# uc.net
KiCad netlist of a schematic drawn in Altium Designer
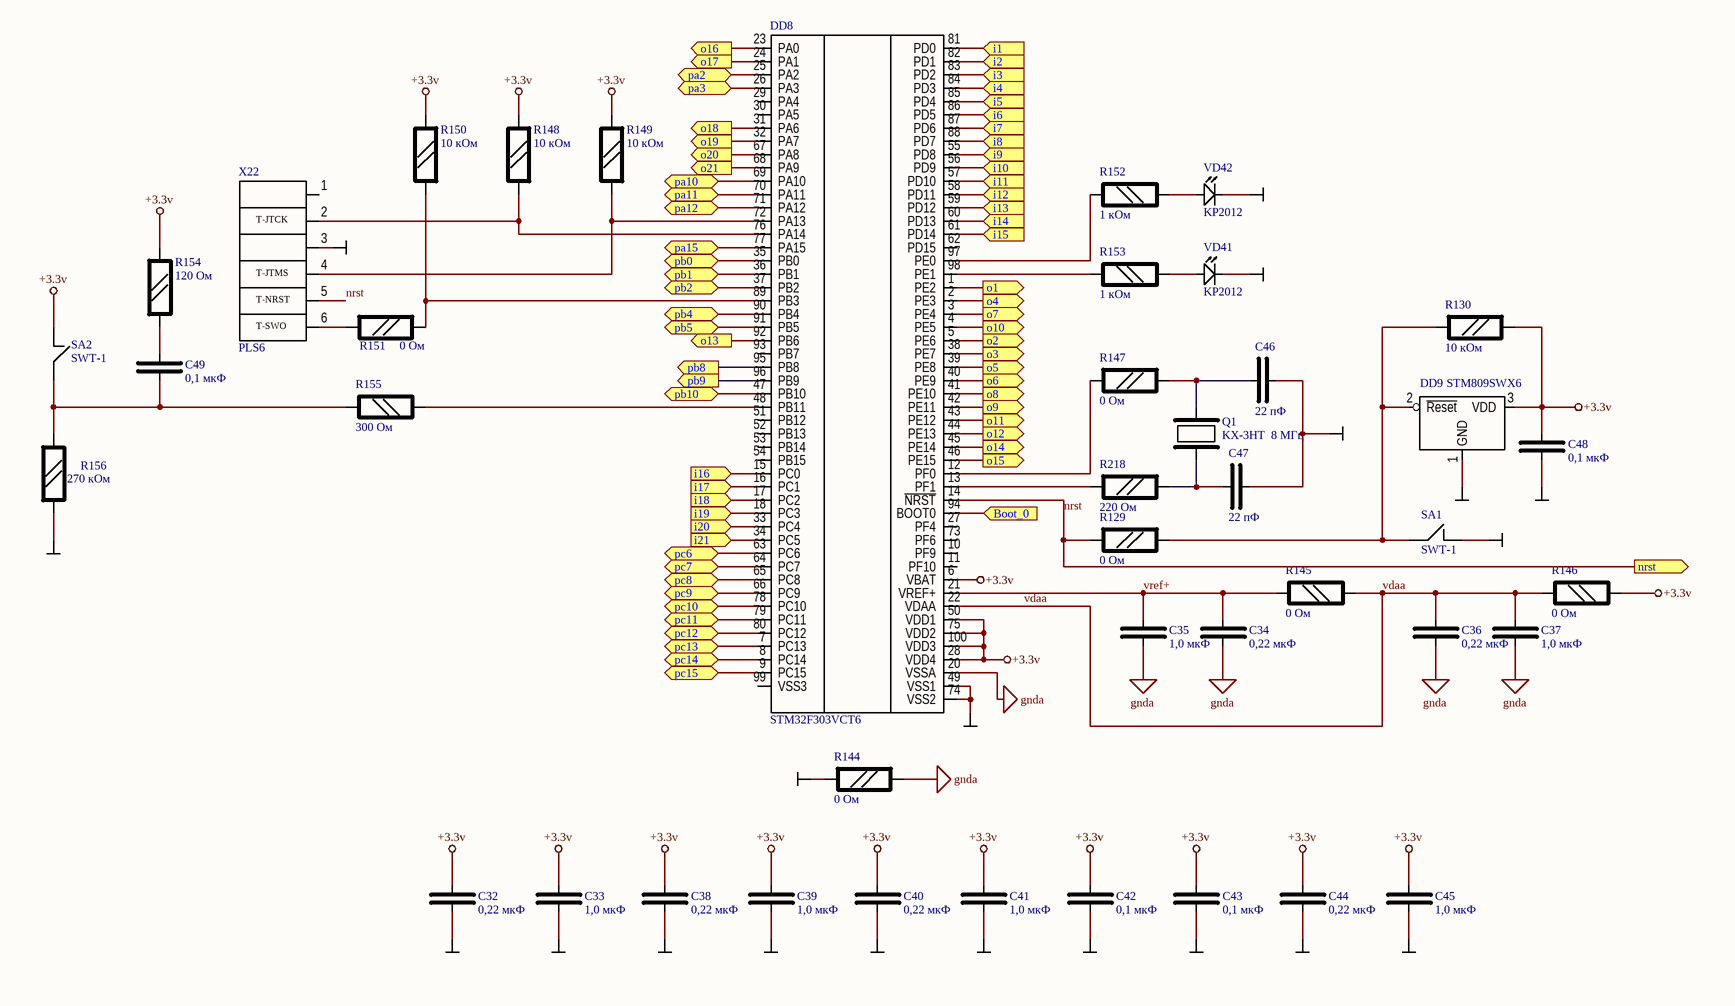
[diagram p0: uc.SchDoc]

(export (version "E")
  (design (tool "Eeschema 10.0.6"))
  (components
    (comp (ref "C32")
      (value "0,22 мкФ")
      (footprint "SMD0805CAP")
      (description "Чип конденсатор 0805")
      (fields (field (name "VOLTAGE") "50V"))
      (libsource (lib "SL02_22F") (part "C0805"))
    )
    (comp (ref "C33")
      (value "1,0 мкФ")
      (footprint "SMD0805CAP")
      (description "Чип конденсатор 0805")
      (fields (field (name "VOLTAGE") "50V"))
      (libsource (lib "SL02_22F") (part "C0805"))
    )
    (comp (ref "C34")
      (value "0,22 мкФ")
      (footprint "SMD0805CAP")
      (description "Чип конденсатор 0805")
      (fields (field (name "VOLTAGE") "50V"))
      (libsource (lib "SL02_22F") (part "C0805"))
    )
    (comp (ref "C35")
      (value "1,0 мкФ")
      (footprint "SMD0805CAP")
      (description "Чип конденсатор 0805")
      (fields (field (name "VOLTAGE") "50V"))
      (libsource (lib "SL02_22F") (part "C0805"))
    )
    (comp (ref "C36")
      (value "0,22 мкФ")
      (footprint "SMD0805CAP")
      (description "Чип конденсатор 0805")
      (fields (field (name "VOLTAGE") "50V"))
      (libsource (lib "SL02_22F") (part "C0805"))
    )
    (comp (ref "C37")
      (value "1,0 мкФ")
      (footprint "SMD0805CAP")
      (description "Чип конденсатор 0805")
      (fields (field (name "VOLTAGE") "50V"))
      (libsource (lib "SL02_22F") (part "C0805"))
    )
    (comp (ref "C38")
      (value "0,22 мкФ")
      (footprint "SMD0805CAP")
      (description "Чип конденсатор 0805")
      (fields (field (name "VOLTAGE") "50V"))
      (libsource (lib "SL02_22F") (part "C0805"))
    )
    (comp (ref "C39")
      (value "1,0 мкФ")
      (footprint "SMD0805CAP")
      (description "Чип конденсатор 0805")
      (fields (field (name "VOLTAGE") "50V"))
      (libsource (lib "SL02_22F") (part "C0805"))
    )
    (comp (ref "C40")
      (value "0,22 мкФ")
      (footprint "SMD0805CAP")
      (description "Чип конденсатор 0805")
      (fields (field (name "VOLTAGE") "50V"))
      (libsource (lib "SL02_22F") (part "C0805"))
    )
    (comp (ref "C41")
      (value "1,0 мкФ")
      (footprint "SMD0805CAP")
      (description "Чип конденсатор 0805")
      (fields (field (name "VOLTAGE") "50V"))
      (libsource (lib "SL02_22F") (part "C0805"))
    )
    (comp (ref "C42")
      (value "0,1 мкФ")
      (footprint "SMD0805CAP")
      (description "Чип конденсатор 0805")
      (fields (field (name "VOLTAGE") "50V"))
      (libsource (lib "SL02_22F") (part "C0805"))
    )
    (comp (ref "C43")
      (value "0,1 мкФ")
      (footprint "SMD0805CAP")
      (description "Чип конденсатор 0805")
      (fields (field (name "VOLTAGE") "50V"))
      (libsource (lib "SL02_22F") (part "C0805"))
    )
    (comp (ref "C44")
      (value "0,22 мкФ")
      (footprint "SMD0805CAP")
      (description "Чип конденсатор 0805")
      (fields (field (name "VOLTAGE") "50V"))
      (libsource (lib "SL02_22F") (part "C0805"))
    )
    (comp (ref "C45")
      (value "1,0 мкФ")
      (footprint "SMD0805CAP")
      (description "Чип конденсатор 0805")
      (fields (field (name "VOLTAGE") "50V"))
      (libsource (lib "SL02_22F") (part "C0805"))
    )
    (comp (ref "C46")
      (value "22 пФ")
      (footprint "SMD0805CAP")
      (description "Чип конденсатор 0805")
      (fields (field (name "VOLTAGE") "50V"))
      (libsource (lib "SL02_22F") (part "C0805"))
    )
    (comp (ref "C47")
      (value "22 пФ")
      (footprint "SMD0805CAP")
      (description "Чип конденсатор 0805")
      (fields (field (name "VOLTAGE") "50V"))
      (libsource (lib "SL02_22F") (part "C0805"))
    )
    (comp (ref "C48")
      (value "0,1 мкФ")
      (footprint "SMD0805CAP")
      (description "Чип конденсатор 0805")
      (fields (field (name "VOLTAGE") "50V"))
      (libsource (lib "SL02_22F") (part "C0805"))
    )
    (comp (ref "C49")
      (value "0,1 мкФ")
      (footprint "SMD0805CAP")
      (description "Чип конденсатор 0805")
      (fields (field (name "VOLTAGE") "50V"))
      (libsource (lib "SL02_22F") (part "C0805"))
    )
    (comp (ref "DD8")
      (value "STM32F303VCT6")
      (footprint "LQFP100")
      (description "ARM Cortex3")
      (libsource (lib "SL02_22F") (part "STM32F303VCT6"))
    )
    (comp (ref "DD9")
      (value "STM809SWX6")
      (footprint "SOT-23")
      (description "Reset генератор")
      (fields (field (name "VOLTAGE") "3V3"))
      (libsource (lib "L02_22F") (part "STM809SWX6"))
    )
    (comp (ref "Q1")
      (value "KX-3HT  8 МГц")
      (footprint "HC49_S")
      (description "Резонатор кварцевый")
      (libsource (lib "SL02_22F") (part "KX-3HT"))
    )
    (comp (ref "R129")
      (value "0 Ом")
      (footprint "SMD0805RES")
      (description "Чип резистор 0805")
      (fields (field (name "TOLERANCE") "5%"))
      (libsource (lib "SL02_22F") (part "R0805"))
    )
    (comp (ref "R130")
      (value "10 кОм")
      (footprint "SMD0805RES")
      (description "Чип резистор 0805")
      (fields (field (name "TOLERANCE") "5%"))
      (libsource (lib "SL02_22F") (part "R0805"))
    )
    (comp (ref "R144")
      (value "0 Ом")
      (footprint "SMD0805RES")
      (description "Чип резистор 0805")
      (fields (field (name "TOLERANCE") "5%"))
      (libsource (lib "SL02_22F") (part "R0805"))
    )
    (comp (ref "R145")
      (value "0 Ом")
      (footprint "SMD0805RES")
      (description "Чип резистор 0805")
      (fields (field (name "TOLERANCE") "5%"))
      (libsource (lib "SL02_22F") (part "R0805"))
    )
    (comp (ref "R146")
      (value "0 Ом")
      (footprint "SMD0805RES")
      (description "Чип резистор 0805")
      (fields (field (name "TOLERANCE") "5%"))
      (libsource (lib "SL02_22F") (part "R0805"))
    )
    (comp (ref "R147")
      (value "0 Ом")
      (footprint "SMD0805RES")
      (description "Чип резистор 0805")
      (fields (field (name "TOLERANCE") "5%"))
      (libsource (lib "SL02_22F") (part "R0805"))
    )
    (comp (ref "R148")
      (value "10 кОм")
      (footprint "SMD0805RES")
      (description "Чип резистор 0805")
      (fields (field (name "TOLERANCE") "1%"))
      (libsource (lib "SL02_22F") (part "R0805"))
    )
    (comp (ref "R149")
      (value "10 кОм")
      (footprint "SMD0805RES")
      (description "Чип резистор 0805")
      (fields (field (name "TOLERANCE") "1%"))
      (libsource (lib "SL02_22F") (part "R0805"))
    )
    (comp (ref "R150")
      (value "10 кОм")
      (footprint "SMD0805RES")
      (description "Чип резистор 0805")
      (fields (field (name "TOLERANCE") "1%"))
      (libsource (lib "SL02_22F") (part "R0805"))
    )
    (comp (ref "R151")
      (value "0 Ом")
      (footprint "SMD0805RES")
      (description "Чип резистор 0805")
      (fields (field (name "TOLERANCE") "5%"))
      (libsource (lib "SL02_22F") (part "R0805"))
    )
    (comp (ref "R152")
      (value "1 кОм")
      (footprint "SMD0805RES")
      (description "Чип резистор 0805")
      (fields (field (name "TOLERANCE") "5%"))
      (libsource (lib "SL02_22F") (part "R0805"))
    )
    (comp (ref "R153")
      (value "1 кОм")
      (footprint "SMD0805RES")
      (description "Чип резистор 0805")
      (fields (field (name "TOLERANCE") "5%"))
      (libsource (lib "SL02_22F") (part "R0805"))
    )
    (comp (ref "R154")
      (value "120 Ом")
      (footprint "SMD0805RES")
      (description "Чип резистор 0805")
      (fields (field (name "TOLERANCE") "5%"))
      (libsource (lib "SL02_22F") (part "R0805"))
    )
    (comp (ref "R155")
      (value "300 Ом")
      (footprint "SMD0805RES")
      (description "Чип резистор 0805")
      (fields (field (name "TOLERANCE") "5%"))
      (libsource (lib "SL02_22F") (part "R0805"))
    )
    (comp (ref "R156")
      (value "270 кОм")
      (footprint "SMD0805RES")
      (description "Чип резистор 0805")
      (fields (field (name "TOLERANCE") "5%"))
      (libsource (lib "SL02_22F") (part "R0805"))
    )
    (comp (ref "R218")
      (value "220 Ом")
      (footprint "SMD0805RES")
      (description "Чип резистор 0805")
      (fields (field (name "TOLERANCE") "5%"))
      (libsource (lib "SL02_22F") (part "R0805"))
    )
    (comp (ref "SA1")
      (value "SWT-1")
      (footprint "SWT-1")
      (description "Кнопка тактовая")
      (fields (field (name "VOLTAGE") "12"))
      (libsource (lib "L02_22F") (part "SWT1"))
    )
    (comp (ref "SA2")
      (value "SWT-1")
      (footprint "SWT-1")
      (description "Кнопка тактовая")
      (fields (field (name "VOLTAGE") "12"))
      (libsource (lib "L02_22F") (part "SWT1"))
    )
    (comp (ref "VD41")
      (value "KP2012")
      (footprint "SMD0805DIO_C")
      (description "Чип светодиод 0805")
      (libsource (lib "L02_22F") (part "KP2012_C"))
    )
    (comp (ref "VD42")
      (value "KP2012")
      (footprint "SMD0805DIO_C")
      (description "Чип светодиод 0805")
      (libsource (lib "L02_22F") (part "KP2012_C"))
    )
    (comp (ref "X22")
      (value "PLS6")
      (footprint "PLS6")
      (description "Вилка  PLS 6x2.54")
      (libsource (lib "L02_22F") (part "PLS6"))
    )
  )
  (nets
    (net (code "1") (name "+3.3v") (class "Default")
      (node (ref "C32") (pin "1") (pinfunction "1_1") (pintype "passive"))
      (node (ref "C33") (pin "1") (pinfunction "1_1") (pintype "passive"))
      (node (ref "C38") (pin "1") (pinfunction "1_1") (pintype "passive"))
      (node (ref "C39") (pin "1") (pinfunction "1_1") (pintype "passive"))
      (node (ref "C40") (pin "1") (pinfunction "1_1") (pintype "passive"))
      (node (ref "C41") (pin "1") (pinfunction "1_1") (pintype "passive"))
      (node (ref "C42") (pin "1") (pinfunction "1_1") (pintype "passive"))
      (node (ref "C43") (pin "1") (pinfunction "1_1") (pintype "passive"))
      (node (ref "C44") (pin "1") (pinfunction "1_1") (pintype "passive"))
      (node (ref "C45") (pin "1") (pinfunction "1_1") (pintype "passive"))
      (node (ref "C48") (pin "1") (pinfunction "1_1") (pintype "passive"))
      (node (ref "DD8") (pin "100") (pinfunction "VDD3_100") (pintype "passive"))
      (node (ref "DD8") (pin "28") (pinfunction "VDD4_28") (pintype "passive"))
      (node (ref "DD8") (pin "50") (pinfunction "VDD1_50") (pintype "passive"))
      (node (ref "DD8") (pin "6") (pinfunction "VBAT_6") (pintype "passive"))
      (node (ref "DD8") (pin "75") (pinfunction "VDD2_75") (pintype "passive"))
      (node (ref "DD9") (pin "3") (pinfunction "VDD_3") (pintype "power_in"))
      (node (ref "R130") (pin "2") (pinfunction "2_2") (pintype "passive"))
      (node (ref "R146") (pin "1") (pinfunction "1_1") (pintype "passive"))
      (node (ref "R148") (pin "2") (pinfunction "2_2") (pintype "passive"))
      (node (ref "R149") (pin "2") (pinfunction "2_2") (pintype "passive"))
      (node (ref "R150") (pin "2") (pinfunction "2_2") (pintype "passive"))
      (node (ref "R154") (pin "1") (pinfunction "1_1") (pintype "passive"))
      (node (ref "SA2") (pin "2") (pinfunction "2_2") (pintype "passive"))
    )
    (net (code "2") (name "/i1") (class "Default")
      (node (ref "DD8") (pin "81") (pinfunction "PD0_81") (pintype "passive"))
    )
    (net (code "3") (name "/i2") (class "Default")
      (node (ref "DD8") (pin "82") (pinfunction "PD1_82") (pintype "passive"))
    )
    (net (code "4") (name "/i3") (class "Default")
      (node (ref "DD8") (pin "83") (pinfunction "PD2_83") (pintype "passive"))
    )
    (net (code "5") (name "/i4") (class "Default")
      (node (ref "DD8") (pin "84") (pinfunction "PD3_84") (pintype "passive"))
    )
    (net (code "6") (name "/i5") (class "Default")
      (node (ref "DD8") (pin "85") (pinfunction "PD4_85") (pintype "passive"))
    )
    (net (code "7") (name "/i6") (class "Default")
      (node (ref "DD8") (pin "86") (pinfunction "PD5_86") (pintype "passive"))
    )
    (net (code "8") (name "/i7") (class "Default")
      (node (ref "DD8") (pin "87") (pinfunction "PD6_87") (pintype "passive"))
    )
    (net (code "9") (name "/i8") (class "Default")
      (node (ref "DD8") (pin "88") (pinfunction "PD7_88") (pintype "passive"))
    )
    (net (code "10") (name "/i9") (class "Default")
      (node (ref "DD8") (pin "55") (pinfunction "PD8_55") (pintype "passive"))
    )
    (net (code "11") (name "/i10") (class "Default")
      (node (ref "DD8") (pin "56") (pinfunction "PD9_56") (pintype "passive"))
    )
    (net (code "12") (name "/i11") (class "Default")
      (node (ref "DD8") (pin "57") (pinfunction "PD10_57") (pintype "passive"))
    )
    (net (code "13") (name "/i12") (class "Default")
      (node (ref "DD8") (pin "58") (pinfunction "PD11_58") (pintype "passive"))
    )
    (net (code "14") (name "/i13") (class "Default")
      (node (ref "DD8") (pin "59") (pinfunction "PD12_59") (pintype "passive"))
    )
    (net (code "15") (name "/i14") (class "Default")
      (node (ref "DD8") (pin "60") (pinfunction "PD13_60") (pintype "passive"))
    )
    (net (code "16") (name "/i15") (class "Default")
      (node (ref "DD8") (pin "61") (pinfunction "PD14_61") (pintype "passive"))
    )
    (net (code "17") (name "/i16") (class "Default")
      (node (ref "DD8") (pin "15") (pinfunction "PC0_15") (pintype "passive"))
    )
    (net (code "18") (name "/i17") (class "Default")
      (node (ref "DD8") (pin "16") (pinfunction "PC1_16") (pintype "passive"))
    )
    (net (code "19") (name "/i18") (class "Default")
      (node (ref "DD8") (pin "17") (pinfunction "PC2_17") (pintype "passive"))
    )
    (net (code "20") (name "/i19") (class "Default")
      (node (ref "DD8") (pin "18") (pinfunction "PC3_18") (pintype "passive"))
    )
    (net (code "21") (name "/i20") (class "Default")
      (node (ref "DD8") (pin "33") (pinfunction "PC4_33") (pintype "passive"))
    )
    (net (code "22") (name "/i21") (class "Default")
      (node (ref "DD8") (pin "34") (pinfunction "PC5_34") (pintype "passive"))
    )
    (net (code "23") (name "/nrst") (class "Default")
      (node (ref "DD8") (pin "14") (pinfunction "NRST_14") (pintype "passive"))
      (node (ref "R129") (pin "1") (pinfunction "1_1") (pintype "passive"))
      (node (ref "X22") (pin "5") (pinfunction "5_5") (pintype "passive"))
    )
    (net (code "24") (name "/o1") (class "Default")
      (node (ref "DD8") (pin "1") (pinfunction "PE2_1") (pintype "passive"))
    )
    (net (code "25") (name "/o2") (class "Default")
      (node (ref "DD8") (pin "5") (pinfunction "PE6_5") (pintype "passive"))
    )
    (net (code "26") (name "/o3") (class "Default")
      (node (ref "DD8") (pin "38") (pinfunction "PE7_38") (pintype "passive"))
    )
    (net (code "27") (name "/o4") (class "Default")
      (node (ref "DD8") (pin "2") (pinfunction "PE3_2") (pintype "passive"))
    )
    (net (code "28") (name "/o5") (class "Default")
      (node (ref "DD8") (pin "39") (pinfunction "PE8_39") (pintype "passive"))
    )
    (net (code "29") (name "/o6") (class "Default")
      (node (ref "DD8") (pin "40") (pinfunction "PE9_40") (pintype "passive"))
    )
    (net (code "30") (name "/o7") (class "Default")
      (node (ref "DD8") (pin "3") (pinfunction "PE4_3") (pintype "passive"))
    )
    (net (code "31") (name "/o8") (class "Default")
      (node (ref "DD8") (pin "41") (pinfunction "PE10_41") (pintype "passive"))
    )
    (net (code "32") (name "/o9") (class "Default")
      (node (ref "DD8") (pin "42") (pinfunction "PE11_42") (pintype "passive"))
    )
    (net (code "33") (name "/o10") (class "Default")
      (node (ref "DD8") (pin "4") (pinfunction "PE5_4") (pintype "passive"))
    )
    (net (code "34") (name "/o11") (class "Default")
      (node (ref "DD8") (pin "43") (pinfunction "PE12_43") (pintype "passive"))
    )
    (net (code "35") (name "/o12") (class "Default")
      (node (ref "DD8") (pin "44") (pinfunction "PE13_44") (pintype "passive"))
    )
    (net (code "36") (name "/o13") (class "Default")
      (node (ref "DD8") (pin "92") (pinfunction "PB6_92") (pintype "passive"))
    )
    (net (code "37") (name "/o14") (class "Default")
      (node (ref "DD8") (pin "45") (pinfunction "PE14_45") (pintype "passive"))
    )
    (net (code "38") (name "/o15") (class "Default")
      (node (ref "DD8") (pin "46") (pinfunction "PE15_46") (pintype "passive"))
    )
    (net (code "39") (name "/o16") (class "Default")
      (node (ref "DD8") (pin "23") (pinfunction "PA0_23") (pintype "passive"))
    )
    (net (code "40") (name "/o17") (class "Default")
      (node (ref "DD8") (pin "24") (pinfunction "PA1_24") (pintype "passive"))
    )
    (net (code "41") (name "/o18") (class "Default")
      (node (ref "DD8") (pin "31") (pinfunction "PA6_31") (pintype "passive"))
    )
    (net (code "42") (name "/o19") (class "Default")
      (node (ref "DD8") (pin "32") (pinfunction "PA7_32") (pintype "passive"))
    )
    (net (code "43") (name "/o20") (class "Default")
      (node (ref "DD8") (pin "67") (pinfunction "PA8_67") (pintype "passive"))
    )
    (net (code "44") (name "/o21") (class "Default")
      (node (ref "DD8") (pin "68") (pinfunction "PA9_68") (pintype "passive"))
    )
    (net (code "45") (name "/pa2") (class "Default")
      (node (ref "DD8") (pin "25") (pinfunction "PA2_25") (pintype "passive"))
    )
    (net (code "46") (name "/pa3") (class "Default")
      (node (ref "DD8") (pin "26") (pinfunction "PA3_26") (pintype "passive"))
    )
    (net (code "47") (name "/pa10") (class "Default")
      (node (ref "DD8") (pin "69") (pinfunction "PA10_69") (pintype "passive"))
    )
    (net (code "48") (name "/pa11") (class "Default")
      (node (ref "DD8") (pin "70") (pinfunction "PA11_70") (pintype "passive"))
    )
    (net (code "49") (name "/pa12") (class "Default")
      (node (ref "DD8") (pin "71") (pinfunction "PA12_71") (pintype "passive"))
    )
    (net (code "50") (name "/pa15") (class "Default")
      (node (ref "DD8") (pin "77") (pinfunction "PA15_77") (pintype "passive"))
    )
    (net (code "51") (name "/pb0") (class "Default")
      (node (ref "DD8") (pin "35") (pinfunction "PB0_35") (pintype "passive"))
    )
    (net (code "52") (name "/pb1") (class "Default")
      (node (ref "DD8") (pin "36") (pinfunction "PB1_36") (pintype "passive"))
    )
    (net (code "53") (name "/pb2") (class "Default")
      (node (ref "DD8") (pin "37") (pinfunction "PB2_37") (pintype "passive"))
    )
    (net (code "54") (name "/pb4") (class "Default")
      (node (ref "DD8") (pin "90") (pinfunction "PB4_90") (pintype "passive"))
    )
    (net (code "55") (name "/pb5") (class "Default")
      (node (ref "DD8") (pin "91") (pinfunction "PB5_91") (pintype "passive"))
    )
    (net (code "56") (name "/pb8") (class "Default")
      (node (ref "DD8") (pin "95") (pinfunction "PB8_95") (pintype "passive"))
    )
    (net (code "57") (name "/pb9") (class "Default")
      (node (ref "DD8") (pin "96") (pinfunction "PB9_96") (pintype "passive"))
    )
    (net (code "58") (name "/pb10") (class "Default")
      (node (ref "DD8") (pin "47") (pinfunction "PB10_47") (pintype "passive"))
    )
    (net (code "59") (name "/pс6") (class "Default")
      (node (ref "DD8") (pin "63") (pinfunction "PC6_63") (pintype "passive"))
    )
    (net (code "60") (name "/pс7") (class "Default")
      (node (ref "DD8") (pin "64") (pinfunction "PC7_64") (pintype "passive"))
    )
    (net (code "61") (name "/pс8") (class "Default")
      (node (ref "DD8") (pin "65") (pinfunction "PC8_65") (pintype "passive"))
    )
    (net (code "62") (name "/pс9") (class "Default")
      (node (ref "DD8") (pin "66") (pinfunction "PC9_66") (pintype "passive"))
    )
    (net (code "63") (name "/pс10") (class "Default")
      (node (ref "DD8") (pin "78") (pinfunction "PC10_78") (pintype "passive"))
    )
    (net (code "64") (name "/pс11") (class "Default")
      (node (ref "DD8") (pin "79") (pinfunction "PC11_79") (pintype "passive"))
    )
    (net (code "65") (name "/pс12") (class "Default")
      (node (ref "DD8") (pin "80") (pinfunction "PC12_80") (pintype "passive"))
    )
    (net (code "66") (name "/pс13") (class "Default")
      (node (ref "DD8") (pin "7") (pinfunction "PC13_7") (pintype "passive"))
    )
    (net (code "67") (name "/pс14") (class "Default")
      (node (ref "DD8") (pin "8") (pinfunction "PC14_8") (pintype "passive"))
    )
    (net (code "68") (name "/pс15") (class "Default")
      (node (ref "DD8") (pin "9") (pinfunction "PC15_9") (pintype "passive"))
    )
    (net (code "69") (name "/vdaa") (class "Default")
      (node (ref "C36") (pin "1") (pinfunction "1_1") (pintype "passive"))
      (node (ref "C37") (pin "1") (pinfunction "1_1") (pintype "passive"))
      (node (ref "DD8") (pin "22") (pinfunction "VDAA_22") (pintype "passive"))
      (node (ref "R145") (pin "1") (pinfunction "1_1") (pintype "passive"))
      (node (ref "R146") (pin "2") (pinfunction "2_2") (pintype "passive"))
    )
    (net (code "70") (name "/vref+") (class "Default")
      (node (ref "C34") (pin "1") (pinfunction "1_1") (pintype "passive"))
      (node (ref "C35") (pin "1") (pinfunction "1_1") (pintype "passive"))
      (node (ref "DD8") (pin "21") (pinfunction "VREF+_21") (pintype "passive"))
      (node (ref "R145") (pin "2") (pinfunction "2_2") (pintype "passive"))
    )
    (net (code "71") (name "/Вооt_0") (class "Default")
      (node (ref "DD8") (pin "94") (pinfunction "BOOT0_94") (pintype "passive"))
    )
    (net (code "72") (name "GND") (class "Default")
      (node (ref "C32") (pin "2") (pinfunction "2_2") (pintype "passive"))
      (node (ref "C33") (pin "2") (pinfunction "2_2") (pintype "passive"))
      (node (ref "C38") (pin "2") (pinfunction "2_2") (pintype "passive"))
      (node (ref "C39") (pin "2") (pinfunction "2_2") (pintype "passive"))
      (node (ref "C40") (pin "2") (pinfunction "2_2") (pintype "passive"))
      (node (ref "C41") (pin "2") (pinfunction "2_2") (pintype "passive"))
      (node (ref "C42") (pin "2") (pinfunction "2_2") (pintype "passive"))
      (node (ref "C43") (pin "2") (pinfunction "2_2") (pintype "passive"))
      (node (ref "C44") (pin "2") (pinfunction "2_2") (pintype "passive"))
      (node (ref "C45") (pin "2") (pinfunction "2_2") (pintype "passive"))
      (node (ref "C46") (pin "2") (pinfunction "2_2") (pintype "passive"))
      (node (ref "C47") (pin "2") (pinfunction "2_2") (pintype "passive"))
      (node (ref "C48") (pin "2") (pinfunction "2_2") (pintype "passive"))
      (node (ref "DD8") (pin "49") (pinfunction "VSS1_49") (pintype "passive"))
      (node (ref "DD8") (pin "74") (pinfunction "VSS2_74") (pintype "passive"))
      (node (ref "DD9") (pin "1") (pinfunction "GND_1") (pintype "power_in"))
      (node (ref "R144") (pin "1") (pinfunction "1_1") (pintype "passive"))
      (node (ref "R156") (pin "2") (pinfunction "2_2") (pintype "passive"))
      (node (ref "SA1") (pin "2") (pinfunction "2_2") (pintype "passive"))
      (node (ref "VD41") (pin "1") (pinfunction "Cathode_1") (pintype "passive"))
      (node (ref "VD42") (pin "1") (pinfunction "Cathode_1") (pintype "passive"))
      (node (ref "X22") (pin "3") (pinfunction "3_3") (pintype "passive"))
    )
    (net (code "73") (name "Net-(C46-Pad1)") (class "Default")
      (node (ref "C46") (pin "1") (pinfunction "1_1") (pintype "passive"))
      (node (ref "Q1") (pin "1") (pinfunction "1_1") (pintype "passive"))
      (node (ref "R147") (pin "2") (pinfunction "2_2") (pintype "passive"))
    )
    (net (code "74") (name "Net-(C47-Pad1)") (class "Default")
      (node (ref "C47") (pin "1") (pinfunction "1_1") (pintype "passive"))
      (node (ref "Q1") (pin "2") (pinfunction "2_2") (pintype "passive"))
      (node (ref "R218") (pin "2") (pinfunction "2_2") (pintype "passive"))
    )
    (net (code "75") (name "Net-(C49-Pad1)") (class "Default")
      (node (ref "C49") (pin "1") (pinfunction "1_1") (pintype "passive"))
      (node (ref "R154") (pin "2") (pinfunction "2_2") (pintype "passive"))
    )
    (net (code "76") (name "Net-(C49-Pad2)") (class "Default")
      (node (ref "C49") (pin "2") (pinfunction "2_2") (pintype "passive"))
      (node (ref "R155") (pin "2") (pinfunction "2_2") (pintype "passive"))
      (node (ref "R156") (pin "1") (pinfunction "1_1") (pintype "passive"))
      (node (ref "SA2") (pin "1") (pinfunction "1_1") (pintype "passive"))
    )
    (net (code "77") (name "Net-(DD8-PA13)") (class "Default")
      (node (ref "DD8") (pin "72") (pinfunction "PA13_72") (pintype "passive"))
      (node (ref "R149") (pin "1") (pinfunction "1_1") (pintype "passive"))
      (node (ref "X22") (pin "4") (pinfunction "4_4") (pintype "passive"))
    )
    (net (code "78") (name "Net-(DD8-PA14)") (class "Default")
      (node (ref "DD8") (pin "76") (pinfunction "PA14_76") (pintype "passive"))
      (node (ref "R148") (pin "1") (pinfunction "1_1") (pintype "passive"))
      (node (ref "X22") (pin "2") (pinfunction "2_2") (pintype "passive"))
    )
    (net (code "79") (name "Net-(DD8-PB3)") (class "Default")
      (node (ref "DD8") (pin "89") (pinfunction "PB3_89") (pintype "passive"))
      (node (ref "R150") (pin "1") (pinfunction "1_1") (pintype "passive"))
      (node (ref "R151") (pin "2") (pinfunction "2_2") (pintype "passive"))
    )
    (net (code "80") (name "Net-(DD8-PB11)") (class "Default")
      (node (ref "DD8") (pin "48") (pinfunction "PB11_48") (pintype "passive"))
      (node (ref "R155") (pin "1") (pinfunction "1_1") (pintype "passive"))
    )
    (net (code "81") (name "Net-(DD8-PE0)") (class "Default")
      (node (ref "DD8") (pin "97") (pinfunction "PE0_97") (pintype "passive"))
      (node (ref "R152") (pin "1") (pinfunction "1_1") (pintype "passive"))
    )
    (net (code "82") (name "Net-(DD8-PE1)") (class "Default")
      (node (ref "DD8") (pin "98") (pinfunction "PE1_98") (pintype "passive"))
      (node (ref "R153") (pin "1") (pinfunction "1_1") (pintype "passive"))
    )
    (net (code "83") (name "Net-(DD8-PF0)") (class "Default")
      (node (ref "DD8") (pin "12") (pinfunction "PF0_12") (pintype "passive"))
      (node (ref "R147") (pin "1") (pinfunction "1_1") (pintype "passive"))
    )
    (net (code "84") (name "Net-(DD8-PF1)") (class "Default")
      (node (ref "DD8") (pin "13") (pinfunction "PF1_13") (pintype "passive"))
      (node (ref "R218") (pin "1") (pinfunction "1_1") (pintype "passive"))
    )
    (net (code "85") (name "Net-(DD9-Reset)") (class "Default")
      (node (ref "DD9") (pin "2") (pinfunction "Reset_2") (pintype "output"))
      (node (ref "R129") (pin "2") (pinfunction "2_2") (pintype "passive"))
      (node (ref "R130") (pin "1") (pinfunction "1_1") (pintype "passive"))
      (node (ref "SA1") (pin "1") (pinfunction "1_1") (pintype "passive"))
    )
    (net (code "86") (name "Net-(R151-Pad1)") (class "Default")
      (node (ref "R151") (pin "1") (pinfunction "1_1") (pintype "passive"))
      (node (ref "X22") (pin "6") (pinfunction "6_6") (pintype "passive"))
    )
    (net (code "87") (name "Net-(VD41-Anode)") (class "Default")
      (node (ref "R153") (pin "2") (pinfunction "2_2") (pintype "passive"))
      (node (ref "VD41") (pin "2") (pinfunction "Anode_2") (pintype "passive"))
    )
    (net (code "88") (name "Net-(VD42-Anode)") (class "Default")
      (node (ref "R152") (pin "2") (pinfunction "2_2") (pintype "passive"))
      (node (ref "VD42") (pin "2") (pinfunction "Anode_2") (pintype "passive"))
    )
    (net (code "89") (name "gnda") (class "Default")
      (node (ref "C34") (pin "2") (pinfunction "2_2") (pintype "passive"))
      (node (ref "C35") (pin "2") (pinfunction "2_2") (pintype "passive"))
      (node (ref "C36") (pin "2") (pinfunction "2_2") (pintype "passive"))
      (node (ref "C37") (pin "2") (pinfunction "2_2") (pintype "passive"))
      (node (ref "DD8") (pin "20") (pinfunction "VSSA_20") (pintype "passive"))
      (node (ref "R144") (pin "2") (pinfunction "2_2") (pintype "passive"))
    )
    (net (code "90") (name "unconnected-(DD8-PA4-Pad29)") (class "Default")
      (node (ref "DD8") (pin "29") (pinfunction "PA4_29") (pintype "passive"))
    )
    (net (code "91") (name "unconnected-(DD8-PA5-Pad30)") (class "Default")
      (node (ref "DD8") (pin "30") (pinfunction "PA5_30") (pintype "passive"))
    )
    (net (code "92") (name "unconnected-(DD8-PB7-Pad93)") (class "Default")
      (node (ref "DD8") (pin "93") (pinfunction "PB7_93") (pintype "passive"))
    )
    (net (code "93") (name "unconnected-(DD8-PB12-Pad51)") (class "Default")
      (node (ref "DD8") (pin "51") (pinfunction "PB12_51") (pintype "passive"))
    )
    (net (code "94") (name "unconnected-(DD8-PB13-Pad52)") (class "Default")
      (node (ref "DD8") (pin "52") (pinfunction "PB13_52") (pintype "passive"))
    )
    (net (code "95") (name "unconnected-(DD8-PB14-Pad53)") (class "Default")
      (node (ref "DD8") (pin "53") (pinfunction "PB14_53") (pintype "passive"))
    )
    (net (code "96") (name "unconnected-(DD8-PB15-Pad54)") (class "Default")
      (node (ref "DD8") (pin "54") (pinfunction "PB15_54") (pintype "passive"))
    )
    (net (code "97") (name "unconnected-(DD8-PD15-Pad62)") (class "Default")
      (node (ref "DD8") (pin "62") (pinfunction "PD15_62") (pintype "passive"))
    )
    (net (code "98") (name "unconnected-(DD8-PF4-Pad27)") (class "Default")
      (node (ref "DD8") (pin "27") (pinfunction "PF4_27") (pintype "passive"))
    )
    (net (code "99") (name "unconnected-(DD8-PF6-Pad73)") (class "Default")
      (node (ref "DD8") (pin "73") (pinfunction "PF6_73") (pintype "passive"))
    )
    (net (code "100") (name "unconnected-(DD8-PF9-Pad10)") (class "Default")
      (node (ref "DD8") (pin "10") (pinfunction "PF9_10") (pintype "passive"))
    )
    (net (code "101") (name "unconnected-(DD8-PF10-Pad11)") (class "Default")
      (node (ref "DD8") (pin "11") (pinfunction "PF10_11") (pintype "passive"))
    )
    (net (code "102") (name "unconnected-(DD8-VSS3-Pad99)") (class "Default")
      (node (ref "DD8") (pin "99") (pinfunction "VSS3_99") (pintype "passive"))
    )
    (net (code "103") (name "unconnected-(X22-Pad1)") (class "Default")
      (node (ref "X22") (pin "1") (pinfunction "1_1") (pintype "passive"))
    )
  )
)
